# design.net
KiCad netlist of a schematic drawn in Altium Designer
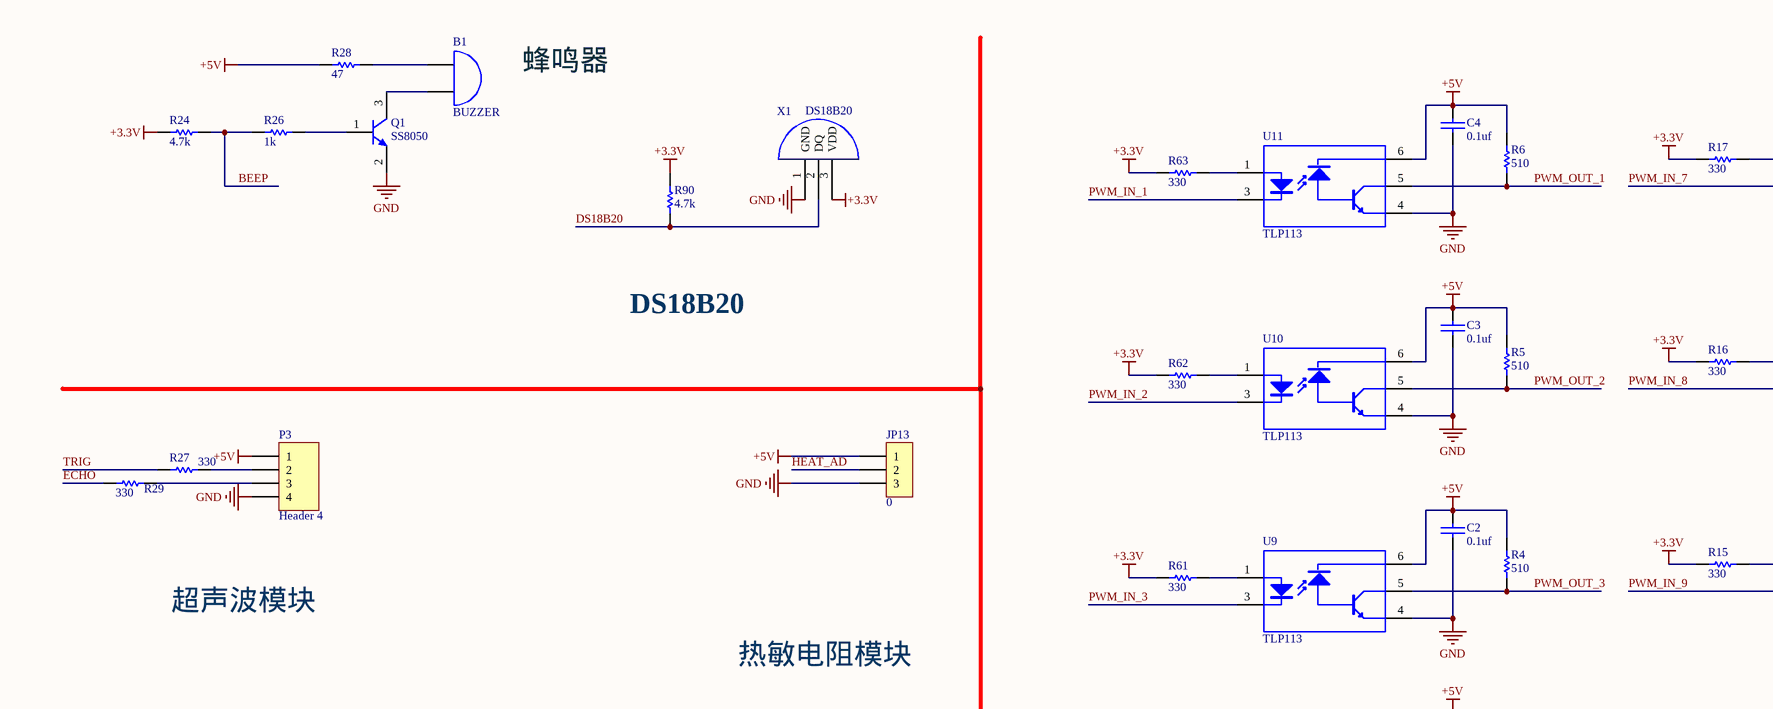
[diagram p0: 原理图.SchDoc, top left]
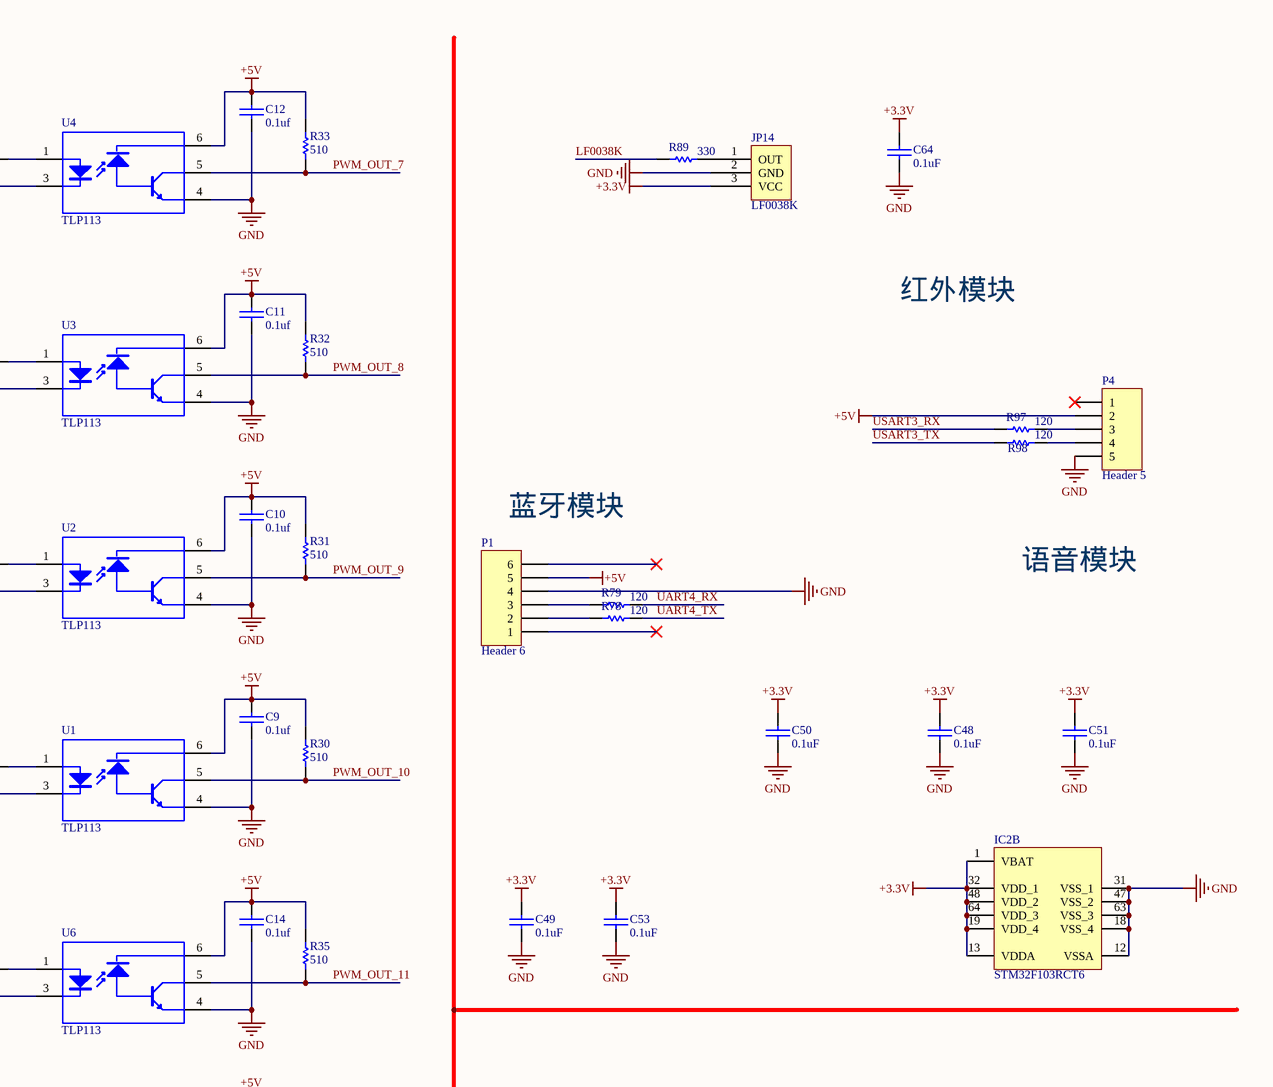
[diagram p1: 原理图.SchDoc, top right]
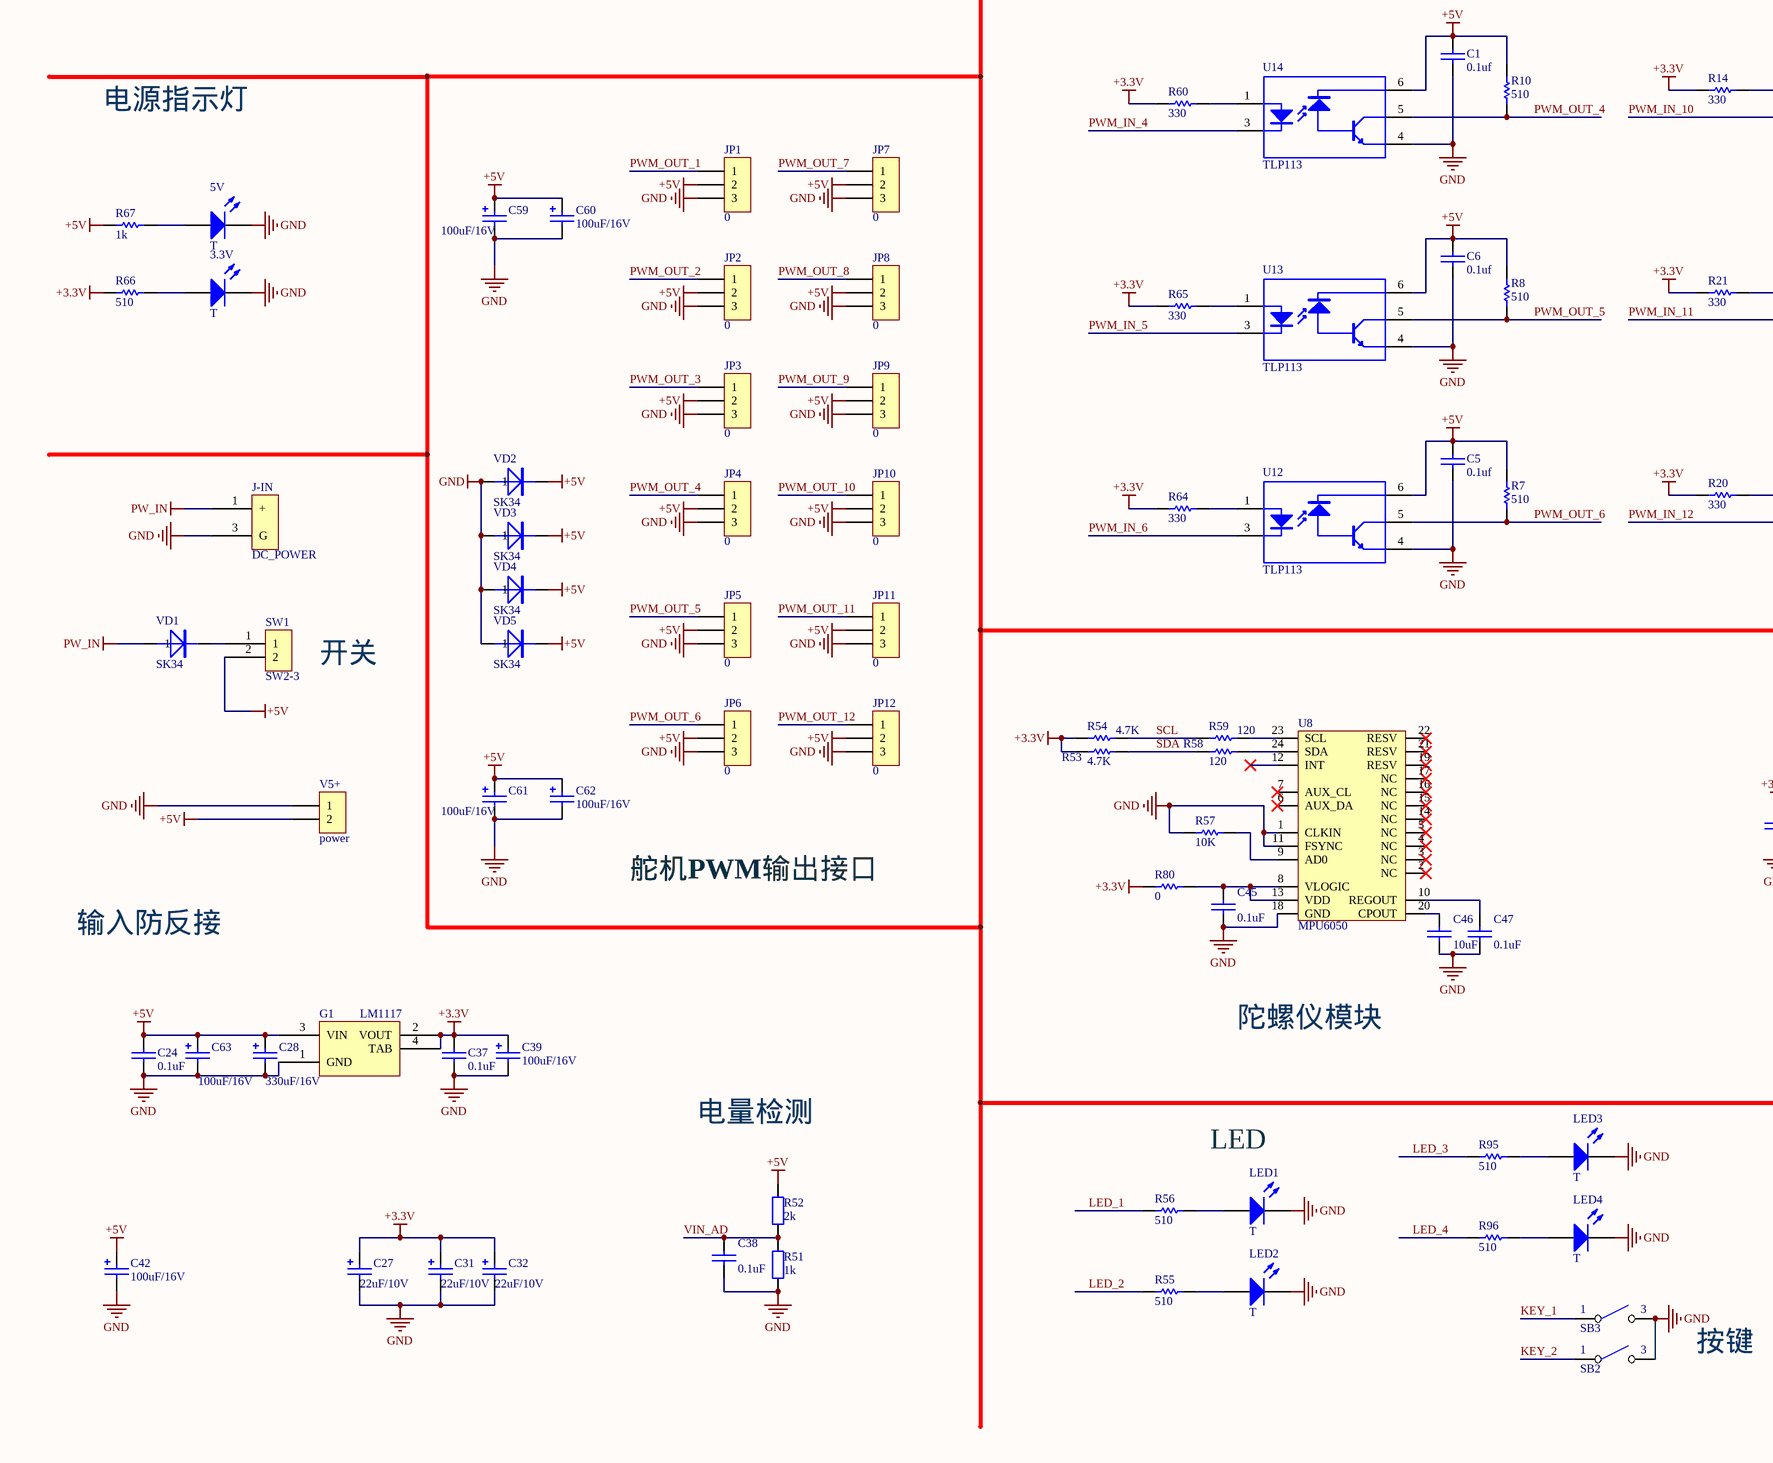
[diagram p2: 原理图.SchDoc, bottom left]
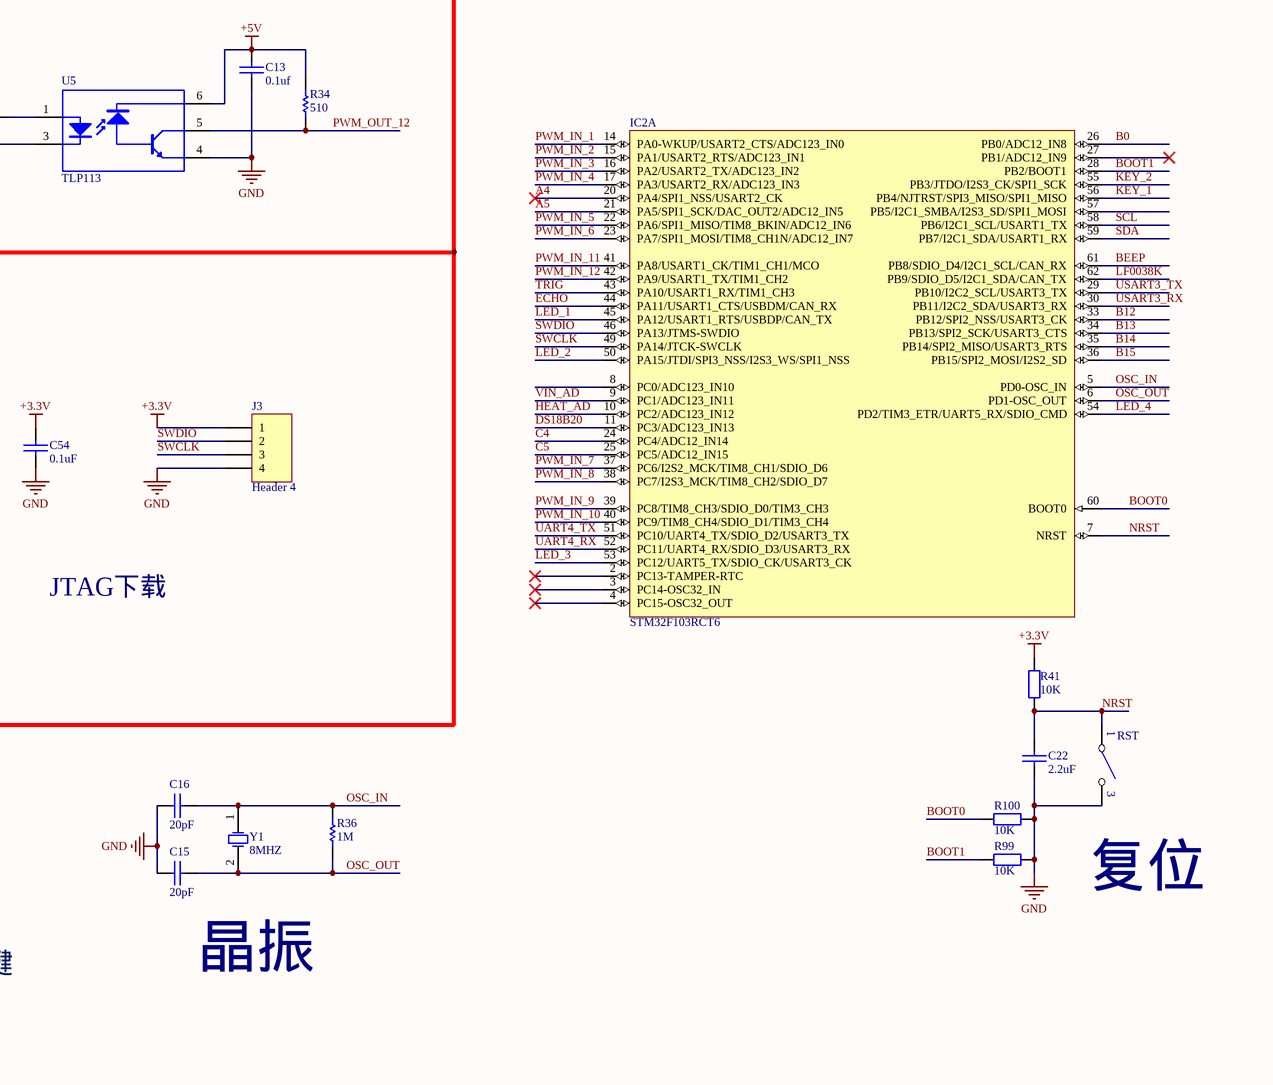
[diagram p3: 原理图.SchDoc, bottom right]

(export (version "E")
  (design (tool "Eeschema 10.0.6"))
  (components
    (comp (ref "3.3V")
      (value "T")
      (footprint "LED-0805")
      (description "Typical INFRARED GaAs LED")
      (fields (field (name "PUBLISHER") "Altium Limited"))
      (libsource (lib "Integrated_Library_1") (part "LED0"))
    )
    (comp (ref "5V")
      (value "T")
      (footprint "LED-0805")
      (description "Typical INFRARED GaAs LED")
      (fields (field (name "PUBLISHER") "Altium Limited"))
      (libsource (lib "Integrated_Library_1") (part "LED0"))
    )
    (comp (ref "B1")
      (value "BUZZER")
      (footprint "BUZZER-5V")
      (description "Bell")
      (libsource (lib "Integrated_Library_1") (part "BELL"))
    )
    (comp (ref "C1")
      (value "0.1uf")
      (footprint "0805")
      (libsource (lib "Integrated_Library_1") (part "CAP_1"))
    )
    (comp (ref "C2")
      (value "0.1uf")
      (footprint "0805")
      (libsource (lib "Integrated_Library_1") (part "CAP_1"))
    )
    (comp (ref "C3")
      (value "0.1uf")
      (footprint "0805")
      (libsource (lib "Integrated_Library_1") (part "CAP_1"))
    )
    (comp (ref "C4")
      (value "0.1uf")
      (footprint "0805")
      (libsource (lib "Integrated_Library_1") (part "CAP_1"))
    )
    (comp (ref "C5")
      (value "0.1uf")
      (footprint "0805")
      (libsource (lib "Integrated_Library_1") (part "CAP_1"))
    )
    (comp (ref "C6")
      (value "0.1uf")
      (footprint "0805")
      (libsource (lib "Integrated_Library_1") (part "CAP_1"))
    )
    (comp (ref "C9")
      (value "0.1uf")
      (footprint "0805")
      (libsource (lib "Integrated_Library_1") (part "CAP_1"))
    )
    (comp (ref "C10")
      (value "0.1uf")
      (footprint "0805")
      (libsource (lib "Integrated_Library_1") (part "CAP_1"))
    )
    (comp (ref "C11")
      (value "0.1uf")
      (footprint "0805")
      (libsource (lib "Integrated_Library_1") (part "CAP_1"))
    )
    (comp (ref "C12")
      (value "0.1uf")
      (footprint "0805")
      (libsource (lib "Integrated_Library_1") (part "CAP_1"))
    )
    (comp (ref "C13")
      (value "0.1uf")
      (footprint "0805")
      (libsource (lib "Integrated_Library_1") (part "CAP_1"))
    )
    (comp (ref "C14")
      (value "0.1uf")
      (footprint "0805")
      (libsource (lib "Integrated_Library_1") (part "CAP_1"))
    )
    (comp (ref "C15")
      (value "20pF")
      (footprint "0805")
      (libsource (lib "Integrated_Library_1") (part "CAP_1"))
    )
    (comp (ref "C16")
      (value "20pF")
      (footprint "0805")
      (libsource (lib "Integrated_Library_1") (part "CAP_1"))
    )
    (comp (ref "C22")
      (value "2.2uF")
      (footprint "0805")
      (libsource (lib "Integrated_Library_1") (part "CAP"))
    )
    (comp (ref "C24")
      (value "0.1uF")
      (footprint "0805")
      (libsource (lib "Integrated_Library_1") (part "CAP_1"))
    )
    (comp (ref "C27")
      (value "22uF/10V")
      (footprint "3528-B")
      (description "Capacitor")
      (libsource (lib "Integrated_Library_1") (part "ELECTRO1"))
    )
    (comp (ref "C28")
      (value "330uF/16V")
      (footprint "CSMD-100U50V")
      (description "Capacitor")
      (libsource (lib "Integrated_Library_1") (part "ELECTRO1"))
    )
    (comp (ref "C31")
      (value "22uF/10V")
      (footprint "3528-B")
      (description "Capacitor")
      (libsource (lib "Integrated_Library_1") (part "ELECTRO1"))
    )
    (comp (ref "C32")
      (value "22uF/10V")
      (footprint "3528-B")
      (description "Capacitor")
      (libsource (lib "Integrated_Library_1") (part "ELECTRO1"))
    )
    (comp (ref "C37")
      (value "0.1uF")
      (footprint "0805")
      (libsource (lib "Integrated_Library_1") (part "CAP_1"))
    )
    (comp (ref "C38")
      (value "0.1uF")
      (footprint "0805")
      (libsource (lib "Integrated_Library_1") (part "CAP_1"))
    )
    (comp (ref "C39")
      (value "100uF/16V")
      (footprint "7243-D")
      (description "Capacitor")
      (libsource (lib "Integrated_Library_1") (part "ELECTRO1"))
    )
    (comp (ref "C42")
      (value "100uF/16V")
      (footprint "7243-D")
      (description "Capacitor")
      (libsource (lib "Integrated_Library_1") (part "ELECTRO1"))
    )
    (comp (ref "C45")
      (value "0.1uF")
      (footprint "0805")
      (libsource (lib "Integrated_Library_1") (part "CAP_1"))
    )
    (comp (ref "C46")
      (value "10uF")
      (footprint "0805")
      (libsource (lib "Integrated_Library_1") (part "CAP_1"))
    )
    (comp (ref "C47")
      (value "0.1uF")
      (footprint "0805")
      (libsource (lib "Integrated_Library_1") (part "CAP_1"))
    )
    (comp (ref "C48")
      (value "0.1uF")
      (footprint "0805")
      (libsource (lib "Integrated_Library_1") (part "CAP"))
    )
    (comp (ref "C49")
      (value "0.1uF")
      (footprint "0805")
      (libsource (lib "Integrated_Library_1") (part "CAP"))
    )
    (comp (ref "C50")
      (value "0.1uF")
      (footprint "0805")
      (libsource (lib "Integrated_Library_1") (part "CAP"))
    )
    (comp (ref "C51")
      (value "0.1uF")
      (footprint "0805")
      (libsource (lib "Integrated_Library_1") (part "CAP"))
    )
    (comp (ref "C53")
      (value "0.1uF")
      (footprint "0805")
      (libsource (lib "Integrated_Library_1") (part "CAP"))
    )
    (comp (ref "C54")
      (value "0.1uF")
      (footprint "0805")
      (libsource (lib "Integrated_Library_1") (part "CAP"))
    )
    (comp (ref "C59")
      (value "100uF/16V")
      (footprint "7243-D")
      (description "Capacitor")
      (libsource (lib "Integrated_Library_1") (part "ELECTRO1"))
    )
    (comp (ref "C60")
      (value "100uF/16V")
      (footprint "7243-D")
      (description "Capacitor")
      (libsource (lib "Integrated_Library_1") (part "ELECTRO1"))
    )
    (comp (ref "C61")
      (value "100uF/16V")
      (footprint "7243-D")
      (description "Capacitor")
      (libsource (lib "Integrated_Library_1") (part "ELECTRO1"))
    )
    (comp (ref "C62")
      (value "100uF/16V")
      (footprint "7243-D")
      (description "Capacitor")
      (libsource (lib "Integrated_Library_1") (part "ELECTRO1"))
    )
    (comp (ref "C63")
      (value "100uF/16V")
      (footprint "7243-D")
      (description "Capacitor")
      (libsource (lib "Integrated_Library_1") (part "ELECTRO1"))
    )
    (comp (ref "C64")
      (value "0.1uF")
      (footprint "0805")
      (libsource (lib "Integrated_Library_1") (part "CAP"))
    )
    (comp (ref "G1") (value "LM1117") (footprint "SOT223-2.3") (libsource (lib "EIC-Sch-N") (part "LM1117")))
    (comp (ref "IC2")
      (value "STM32F103RCT6")
      (footprint "TQFP64-0.5")
      (libsource (lib "altium-import") (part "root_0_STM32F103RCT6_"))
    )
    (comp (ref "J-IN")
      (value "DC_POWER")
      (footprint "DC-005 5.5-2.1")
      (libsource (lib "Integrated_Library_1") (part "DC_POWER"))
    )
    (comp (ref "J3")
      (value "Header 4")
      (footprint "HDR1X4")
      (description "Header, 4-Pin")
      (fields (field (name "PUBLISHER") "Altium Limited"))
      (libsource (lib "Miscellaneous Connectors") (part "Header 4"))
    )
    (comp (ref "JP1")
      (value "0")
      (footprint "SIP3-2.54")
      (description "Connector")
      (libsource (lib "Integrated_Library_1") (part "CON3"))
    )
    (comp (ref "JP2")
      (value "0")
      (footprint "SIP3-2.54")
      (description "Connector")
      (libsource (lib "Integrated_Library_1") (part "CON3"))
    )
    (comp (ref "JP3")
      (value "0")
      (footprint "SIP3-2.54")
      (description "Connector")
      (libsource (lib "Integrated_Library_1") (part "CON3"))
    )
    (comp (ref "JP4")
      (value "0")
      (footprint "SIP3-2.54")
      (description "Connector")
      (libsource (lib "Integrated_Library_1") (part "CON3"))
    )
    (comp (ref "JP5")
      (value "0")
      (footprint "SIP3-2.54")
      (description "Connector")
      (libsource (lib "Integrated_Library_1") (part "CON3"))
    )
    (comp (ref "JP6")
      (value "0")
      (footprint "SIP3-2.54")
      (description "Connector")
      (libsource (lib "Integrated_Library_1") (part "CON3"))
    )
    (comp (ref "JP7")
      (value "0")
      (footprint "SIP3-2.54")
      (description "Connector")
      (libsource (lib "Integrated_Library_1") (part "CON3"))
    )
    (comp (ref "JP8")
      (value "0")
      (footprint "SIP3-2.54")
      (description "Connector")
      (libsource (lib "Integrated_Library_1") (part "CON3"))
    )
    (comp (ref "JP9")
      (value "0")
      (footprint "SIP3-2.54")
      (description "Connector")
      (libsource (lib "Integrated_Library_1") (part "CON3"))
    )
    (comp (ref "JP10")
      (value "0")
      (footprint "SIP3-2.54")
      (description "Connector")
      (libsource (lib "Integrated_Library_1") (part "CON3"))
    )
    (comp (ref "JP11")
      (value "0")
      (footprint "SIP3-2.54")
      (description "Connector")
      (libsource (lib "Integrated_Library_1") (part "CON3"))
    )
    (comp (ref "JP12")
      (value "0")
      (footprint "SIP3-2.54")
      (description "Connector")
      (libsource (lib "Integrated_Library_1") (part "CON3"))
    )
    (comp (ref "JP13")
      (value "0")
      (footprint "SIP3-2.54")
      (description "Connector")
      (libsource (lib "Integrated_Library_1") (part "CON3"))
    )
    (comp (ref "JP14")
      (value "LF0038K")
      (footprint "LF0038K")
      (libsource (lib "Integrated_Library_1") (part "LF0038K"))
    )
    (comp (ref "LED1")
      (value "T")
      (footprint "LED-0805")
      (description "Typical INFRARED GaAs LED")
      (fields (field (name "PUBLISHER") "Altium Limited"))
      (libsource (lib "Integrated_Library_1") (part "LED0"))
    )
    (comp (ref "LED2")
      (value "T")
      (footprint "LED-0805")
      (description "Typical INFRARED GaAs LED")
      (fields (field (name "PUBLISHER") "Altium Limited"))
      (libsource (lib "Integrated_Library_1") (part "LED0"))
    )
    (comp (ref "LED3")
      (value "T")
      (footprint "LED-0805")
      (description "Typical INFRARED GaAs LED")
      (fields (field (name "PUBLISHER") "Altium Limited"))
      (libsource (lib "Integrated_Library_1") (part "LED0"))
    )
    (comp (ref "LED4")
      (value "T")
      (footprint "LED-0805")
      (description "Typical INFRARED GaAs LED")
      (fields (field (name "PUBLISHER") "Altium Limited"))
      (libsource (lib "Integrated_Library_1") (part "LED0"))
    )
    (comp (ref "P1")
      (value "Header 6")
      (footprint "HDR1X6")
      (description "Header, 6-Pin")
      (fields (field (name "PUBLISHER") "Altium Limited"))
      (libsource (lib "Miscellaneous Connectors") (part "Header 6"))
    )
    (comp (ref "P3")
      (value "Header 4")
      (footprint "HDR1X4")
      (description "Header, 4-Pin")
      (fields (field (name "PUBLISHER") "Altium Limited"))
      (libsource (lib "Miscellaneous Connectors") (part "Header 4"))
    )
    (comp (ref "P4")
      (value "Header 5")
      (footprint "HDR1X5")
      (description "Header, 5-Pin")
      (fields (field (name "PUBLISHER") "Altium Limited"))
      (libsource (lib "Miscellaneous Connectors") (part "Header 5"))
    )
    (comp (ref "Q1")
      (value "SS8050")
      (footprint "SOT-23")
      (description "NPN贴片三极管")
      (fields (field (name "PUBLISHER") "Altium Limited"))
      (libsource (lib "Integrated_Library_1") (part "SS8050"))
    )
    (comp (ref "R4")
      (value "510")
      (footprint "0805")
      (description "Resistor")
      (fields (field (name "PUBLISHER") "Altium Limited"))
      (libsource (lib "Integrated_Library_1") (part "Res1"))
    )
    (comp (ref "R5")
      (value "510")
      (footprint "0805")
      (description "Resistor")
      (fields (field (name "PUBLISHER") "Altium Limited"))
      (libsource (lib "Integrated_Library_1") (part "Res1"))
    )
    (comp (ref "R6")
      (value "510")
      (footprint "0805")
      (description "Resistor")
      (fields (field (name "PUBLISHER") "Altium Limited"))
      (libsource (lib "Integrated_Library_1") (part "Res1"))
    )
    (comp (ref "R7")
      (value "510")
      (footprint "0805")
      (description "Resistor")
      (fields (field (name "PUBLISHER") "Altium Limited"))
      (libsource (lib "Integrated_Library_1") (part "Res1"))
    )
    (comp (ref "R8")
      (value "510")
      (footprint "0805")
      (description "Resistor")
      (fields (field (name "PUBLISHER") "Altium Limited"))
      (libsource (lib "Integrated_Library_1") (part "Res1"))
    )
    (comp (ref "R10")
      (value "510")
      (footprint "0805")
      (description "Resistor")
      (fields (field (name "PUBLISHER") "Altium Limited"))
      (libsource (lib "Integrated_Library_1") (part "Res1"))
    )
    (comp (ref "R14")
      (value "330")
      (footprint "0805")
      (description "Resistor")
      (fields (field (name "PUBLISHER") "Altium Limited"))
      (libsource (lib "Integrated_Library_1") (part "Res1"))
    )
    (comp (ref "R15")
      (value "330")
      (footprint "0805")
      (description "Resistor")
      (fields (field (name "PUBLISHER") "Altium Limited"))
      (libsource (lib "Integrated_Library_1") (part "Res1"))
    )
    (comp (ref "R16")
      (value "330")
      (footprint "0805")
      (description "Resistor")
      (fields (field (name "PUBLISHER") "Altium Limited"))
      (libsource (lib "Integrated_Library_1") (part "Res1"))
    )
    (comp (ref "R17")
      (value "330")
      (footprint "0805")
      (description "Resistor")
      (fields (field (name "PUBLISHER") "Altium Limited"))
      (libsource (lib "Integrated_Library_1") (part "Res1"))
    )
    (comp (ref "R20")
      (value "330")
      (footprint "0805")
      (description "Resistor")
      (fields (field (name "PUBLISHER") "Altium Limited"))
      (libsource (lib "Integrated_Library_1") (part "Res1"))
    )
    (comp (ref "R21")
      (value "330")
      (footprint "0805")
      (description "Resistor")
      (fields (field (name "PUBLISHER") "Altium Limited"))
      (libsource (lib "Integrated_Library_1") (part "Res1"))
    )
    (comp (ref "R24")
      (value "4.7k")
      (footprint "0805")
      (description "Resistor")
      (fields (field (name "PUBLISHER") "Altium Limited"))
      (libsource (lib "Integrated_Library_1") (part "Res1"))
    )
    (comp (ref "R26")
      (value "1k")
      (footprint "0805")
      (description "Resistor")
      (fields (field (name "PUBLISHER") "Altium Limited"))
      (libsource (lib "Integrated_Library_1") (part "Res1"))
    )
    (comp (ref "R27")
      (value "330")
      (footprint "0805")
      (description "Resistor")
      (fields (field (name "PUBLISHER") "Altium Limited"))
      (libsource (lib "Integrated_Library_1") (part "Res1"))
    )
    (comp (ref "R28")
      (value "47")
      (footprint "0805")
      (description "Resistor")
      (fields (field (name "PUBLISHER") "Altium Limited"))
      (libsource (lib "Integrated_Library_1") (part "Res1"))
    )
    (comp (ref "R29")
      (value "330")
      (footprint "0805")
      (description "Resistor")
      (fields (field (name "PUBLISHER") "Altium Limited"))
      (libsource (lib "Integrated_Library_1") (part "Res1"))
    )
    (comp (ref "R30")
      (value "510")
      (footprint "0805")
      (description "Resistor")
      (fields (field (name "PUBLISHER") "Altium Limited"))
      (libsource (lib "Integrated_Library_1") (part "Res1"))
    )
    (comp (ref "R31")
      (value "510")
      (footprint "0805")
      (description "Resistor")
      (fields (field (name "PUBLISHER") "Altium Limited"))
      (libsource (lib "Integrated_Library_1") (part "Res1"))
    )
    (comp (ref "R32")
      (value "510")
      (footprint "0805")
      (description "Resistor")
      (fields (field (name "PUBLISHER") "Altium Limited"))
      (libsource (lib "Integrated_Library_1") (part "Res1"))
    )
    (comp (ref "R33")
      (value "510")
      (footprint "0805")
      (description "Resistor")
      (fields (field (name "PUBLISHER") "Altium Limited"))
      (libsource (lib "Integrated_Library_1") (part "Res1"))
    )
    (comp (ref "R34")
      (value "510")
      (footprint "0805")
      (description "Resistor")
      (fields (field (name "PUBLISHER") "Altium Limited"))
      (libsource (lib "Integrated_Library_1") (part "Res1"))
    )
    (comp (ref "R35")
      (value "510")
      (footprint "0805")
      (description "Resistor")
      (fields (field (name "PUBLISHER") "Altium Limited"))
      (libsource (lib "Integrated_Library_1") (part "Res1"))
    )
    (comp (ref "R36")
      (value "1M")
      (footprint "0805")
      (description "Resistor")
      (fields (field (name "PUBLISHER") "Altium Limited"))
      (libsource (lib "Integrated_Library_1") (part "Res1"))
    )
    (comp (ref "R41")
      (value "10K")
      (footprint "0805")
      (description "Resistor")
      (fields (field (name "PUBLISHER") "Altium Limited"))
      (libsource (lib "Miscellaneous Devices") (part "RES1"))
    )
    (comp (ref "R51")
      (value "1k")
      (footprint "0805")
      (description "Resistor")
      (fields (field (name "PUBLISHER") "Altium Limited"))
      (libsource (lib "Miscellaneous Devices") (part "Res2"))
    )
    (comp (ref "R52")
      (value "2k")
      (footprint "0805")
      (description "Resistor")
      (fields (field (name "PUBLISHER") "Altium Limited"))
      (libsource (lib "Miscellaneous Devices") (part "Res2"))
    )
    (comp (ref "R53")
      (value "4.7K")
      (footprint "0805")
      (description "Resistor")
      (fields (field (name "PUBLISHER") "Altium Limited"))
      (libsource (lib "Integrated_Library_1") (part "Res1"))
    )
    (comp (ref "R54")
      (value "4.7K")
      (footprint "0805")
      (description "Resistor")
      (fields (field (name "PUBLISHER") "Altium Limited"))
      (libsource (lib "Integrated_Library_1") (part "Res1"))
    )
    (comp (ref "R55")
      (value "510")
      (footprint "0805")
      (description "Resistor")
      (fields (field (name "PUBLISHER") "Altium Limited"))
      (libsource (lib "Integrated_Library_1") (part "Res1"))
    )
    (comp (ref "R56")
      (value "510")
      (footprint "0805")
      (description "Resistor")
      (fields (field (name "PUBLISHER") "Altium Limited"))
      (libsource (lib "Integrated_Library_1") (part "Res1"))
    )
    (comp (ref "R57")
      (value "10K")
      (footprint "0805")
      (description "Resistor")
      (fields (field (name "PUBLISHER") "Altium Limited"))
      (libsource (lib "Integrated_Library_1") (part "Res1"))
    )
    (comp (ref "R58")
      (value "120")
      (footprint "0805")
      (description "Resistor")
      (fields (field (name "PUBLISHER") "Altium Limited"))
      (libsource (lib "Integrated_Library_1") (part "Res1"))
    )
    (comp (ref "R59")
      (value "120")
      (footprint "0805")
      (description "Resistor")
      (fields (field (name "PUBLISHER") "Altium Limited"))
      (libsource (lib "Integrated_Library_1") (part "Res1"))
    )
    (comp (ref "R60")
      (value "330")
      (footprint "0805")
      (description "Resistor")
      (fields (field (name "PUBLISHER") "Altium Limited"))
      (libsource (lib "Integrated_Library_1") (part "Res1"))
    )
    (comp (ref "R61")
      (value "330")
      (footprint "0805")
      (description "Resistor")
      (fields (field (name "PUBLISHER") "Altium Limited"))
      (libsource (lib "Integrated_Library_1") (part "Res1"))
    )
    (comp (ref "R62")
      (value "330")
      (footprint "0805")
      (description "Resistor")
      (fields (field (name "PUBLISHER") "Altium Limited"))
      (libsource (lib "Integrated_Library_1") (part "Res1"))
    )
    (comp (ref "R63")
      (value "330")
      (footprint "0805")
      (description "Resistor")
      (fields (field (name "PUBLISHER") "Altium Limited"))
      (libsource (lib "Integrated_Library_1") (part "Res1"))
    )
    (comp (ref "R64")
      (value "330")
      (footprint "0805")
      (description "Resistor")
      (fields (field (name "PUBLISHER") "Altium Limited"))
      (libsource (lib "Integrated_Library_1") (part "Res1"))
    )
    (comp (ref "R65")
      (value "330")
      (footprint "0805")
      (description "Resistor")
      (fields (field (name "PUBLISHER") "Altium Limited"))
      (libsource (lib "Integrated_Library_1") (part "Res1"))
    )
    (comp (ref "R66")
      (value "510")
      (footprint "0805")
      (description "Resistor")
      (fields (field (name "PUBLISHER") "Altium Limited"))
      (libsource (lib "Integrated_Library_1") (part "Res1"))
    )
    (comp (ref "R67")
      (value "1k")
      (footprint "0805")
      (description "Resistor")
      (fields (field (name "PUBLISHER") "Altium Limited"))
      (libsource (lib "Integrated_Library_1") (part "Res1"))
    )
    (comp (ref "R78")
      (value "120")
      (footprint "0805")
      (description "Resistor")
      (fields (field (name "PUBLISHER") "Altium Limited"))
      (libsource (lib "Integrated_Library_1") (part "Res1"))
    )
    (comp (ref "R79")
      (value "120")
      (footprint "0805")
      (description "Resistor")
      (fields (field (name "PUBLISHER") "Altium Limited"))
      (libsource (lib "Integrated_Library_1") (part "Res1"))
    )
    (comp (ref "R80")
      (value "0")
      (footprint "0805")
      (description "Resistor")
      (fields (field (name "PUBLISHER") "Altium Limited"))
      (libsource (lib "Integrated_Library_1") (part "Res1"))
    )
    (comp (ref "R89")
      (value "330")
      (footprint "0805")
      (description "Resistor")
      (fields (field (name "PUBLISHER") "Altium Limited"))
      (libsource (lib "Integrated_Library_1") (part "Res1"))
    )
    (comp (ref "R90")
      (value "4.7k")
      (footprint "0805")
      (description "Resistor")
      (fields (field (name "PUBLISHER") "Altium Limited"))
      (libsource (lib "Integrated_Library_1") (part "Res1"))
    )
    (comp (ref "R95")
      (value "510")
      (footprint "0805")
      (description "Resistor")
      (fields (field (name "PUBLISHER") "Altium Limited"))
      (libsource (lib "Integrated_Library_1") (part "Res1"))
    )
    (comp (ref "R96")
      (value "510")
      (footprint "0805")
      (description "Resistor")
      (fields (field (name "PUBLISHER") "Altium Limited"))
      (libsource (lib "Integrated_Library_1") (part "Res1"))
    )
    (comp (ref "R97")
      (value "120")
      (footprint "0805")
      (description "Resistor")
      (fields (field (name "PUBLISHER") "Altium Limited"))
      (libsource (lib "Integrated_Library_1") (part "Res1"))
    )
    (comp (ref "R98")
      (value "120")
      (footprint "0805")
      (description "Resistor")
      (fields (field (name "PUBLISHER") "Altium Limited"))
      (libsource (lib "Integrated_Library_1") (part "Res1"))
    )
    (comp (ref "R99")
      (value "10K")
      (footprint "0805")
      (description "Resistor")
      (fields (field (name "PUBLISHER") "Altium Limited"))
      (libsource (lib "") (part "RES1_1"))
    )
    (comp (ref "R100")
      (value "10K")
      (footprint "0805")
      (description "Resistor")
      (fields (field (name "PUBLISHER") "Altium Limited"))
      (libsource (lib "") (part "RES1_1"))
    )
    (comp (ref "RST")
      (value "Config")
      (footprint "KEY-SMD")
      (libsource (lib "Integrated_Library_1") (part "KEY1"))
    )
    (comp (ref "SB2")
      (value "Config")
      (footprint "KEY-SMD")
      (libsource (lib "Integrated_Library_1") (part "KEY1"))
    )
    (comp (ref "SB3")
      (value "Config")
      (footprint "KEY-SMD")
      (libsource (lib "Integrated_Library_1") (part "KEY1"))
    )
    (comp (ref "SW1")
      (value "SW2-3")
      (footprint "SS-12F44(1P2T)")
      (libsource (lib "Integrated_Library_1") (part "SW2-3"))
    )
    (comp (ref "U1")
      (value "TLP113")
      (footprint "MFSOP6-5")
      (description "Optoisolator")
      (libsource (lib "Integrated_Library_1") (part "TLP113"))
    )
    (comp (ref "U2")
      (value "TLP113")
      (footprint "MFSOP6-5")
      (description "Optoisolator")
      (libsource (lib "Integrated_Library_1") (part "TLP113"))
    )
    (comp (ref "U3")
      (value "TLP113")
      (footprint "MFSOP6-5")
      (description "Optoisolator")
      (libsource (lib "Integrated_Library_1") (part "TLP113"))
    )
    (comp (ref "U4")
      (value "TLP113")
      (footprint "MFSOP6-5")
      (description "Optoisolator")
      (libsource (lib "Integrated_Library_1") (part "TLP113"))
    )
    (comp (ref "U5")
      (value "TLP113")
      (footprint "MFSOP6-5")
      (description "Optoisolator")
      (libsource (lib "Integrated_Library_1") (part "TLP113"))
    )
    (comp (ref "U6")
      (value "TLP113")
      (footprint "MFSOP6-5")
      (description "Optoisolator")
      (libsource (lib "Integrated_Library_1") (part "TLP113"))
    )
    (comp (ref "U8")
      (value "MPU6050")
      (footprint "QFN24")
      (description "9轴运动处理传感器")
      (libsource (lib "ATK-MPU6050六轴传感器模块") (part "MPU6050"))
    )
    (comp (ref "U9")
      (value "TLP113")
      (footprint "MFSOP6-5")
      (description "Optoisolator")
      (libsource (lib "Integrated_Library_1") (part "TLP113"))
    )
    (comp (ref "U10")
      (value "TLP113")
      (footprint "MFSOP6-5")
      (description "Optoisolator")
      (libsource (lib "Integrated_Library_1") (part "TLP113"))
    )
    (comp (ref "U11")
      (value "TLP113")
      (footprint "MFSOP6-5")
      (description "Optoisolator")
      (libsource (lib "Integrated_Library_1") (part "TLP113"))
    )
    (comp (ref "U12")
      (value "TLP113")
      (footprint "MFSOP6-5")
      (description "Optoisolator")
      (libsource (lib "Integrated_Library_1") (part "TLP113"))
    )
    (comp (ref "U13")
      (value "TLP113")
      (footprint "MFSOP6-5")
      (description "Optoisolator")
      (libsource (lib "Integrated_Library_1") (part "TLP113"))
    )
    (comp (ref "U14")
      (value "TLP113")
      (footprint "MFSOP6-5")
      (description "Optoisolator")
      (libsource (lib "Integrated_Library_1") (part "TLP113"))
    )
    (comp (ref "V5+")
      (value "power")
      (footprint "MKDS2-5.08")
      (description "Connector")
      (libsource (lib "Integrated_Library_1") (part "CON2"))
    )
    (comp (ref "VD1")
      (value "SK34")
      (footprint "SK34-DIODE")
      (libsource (lib "Integrated_Library_1") (part "SK34-DIODE"))
    )
    (comp (ref "VD2")
      (value "SK34")
      (footprint "SK34-DIODE")
      (libsource (lib "Integrated_Library_1") (part "SK34-DIODE"))
    )
    (comp (ref "VD3")
      (value "SK34")
      (footprint "SK34-DIODE")
      (libsource (lib "Integrated_Library_1") (part "SK34-DIODE"))
    )
    (comp (ref "VD4")
      (value "SK34")
      (footprint "SK34-DIODE")
      (libsource (lib "Integrated_Library_1") (part "SK34-DIODE"))
    )
    (comp (ref "VD5")
      (value "SK34")
      (footprint "SK34-DIODE")
      (libsource (lib "Integrated_Library_1") (part "SK34-DIODE"))
    )
    (comp (ref "X1")
      (value "DS18B20")
      (footprint "DS18B20TR")
      (libsource (lib "Integrated_Library_1") (part "DS18B20"))
    )
    (comp (ref "Y1")
      (value "8MHZ")
      (footprint "CRYSTAL-2PIN")
      (description "Crystal Oscillator")
      (fields (field (name "PUBLISHER") "Altium Limited"))
      (libsource (lib "Integrated_Library_1") (part "XTAL_1"))
    )
  )
  (nets
    (net (code "1") (name "+3.3V") (class "Default")
      (node (ref "C27") (pin "1") (pinfunction "1_1") (pintype "passive"))
      (node (ref "C31") (pin "1") (pinfunction "1_1") (pintype "passive"))
      (node (ref "C32") (pin "1") (pinfunction "1_1") (pintype "passive"))
      (node (ref "C37") (pin "1") (pintype "passive"))
      (node (ref "C39") (pin "1") (pinfunction "1_1") (pintype "passive"))
      (node (ref "C48") (pin "1") (pintype "passive"))
      (node (ref "C49") (pin "1") (pintype "passive"))
      (node (ref "C50") (pin "1") (pintype "passive"))
      (node (ref "C51") (pin "1") (pintype "passive"))
      (node (ref "C53") (pin "1") (pintype "passive"))
      (node (ref "C54") (pin "1") (pintype "passive"))
      (node (ref "C64") (pin "1") (pintype "passive"))
      (node (ref "G1") (pin "2") (pinfunction "VOUT_2") (pintype "passive"))
      (node (ref "G1") (pin "4") (pinfunction "TAB_4") (pintype "passive"))
      (node (ref "IC2") (pin "1") (pinfunction "VBAT_1") (pintype "power_in"))
      (node (ref "IC2") (pin "13") (pinfunction "VDDA_13") (pintype "power_in"))
      (node (ref "IC2") (pin "19") (pinfunction "VDD_4_19") (pintype "power_in"))
      (node (ref "IC2") (pin "32") (pinfunction "VDD_1_32") (pintype "power_in"))
      (node (ref "IC2") (pin "48") (pinfunction "VDD_2_48") (pintype "power_in"))
      (node (ref "IC2") (pin "64") (pinfunction "VDD_3_64") (pintype "power_in"))
      (node (ref "J3") (pin "1") (pinfunction "1_1") (pintype "passive"))
      (node (ref "JP14") (pin "3") (pinfunction "VCC_3") (pintype "passive"))
      (node (ref "R14") (pin "1") (pinfunction "1_1") (pintype "passive"))
      (node (ref "R15") (pin "1") (pinfunction "1_1") (pintype "passive"))
      (node (ref "R16") (pin "1") (pinfunction "1_1") (pintype "passive"))
      (node (ref "R17") (pin "1") (pinfunction "1_1") (pintype "passive"))
      (node (ref "R20") (pin "1") (pinfunction "1_1") (pintype "passive"))
      (node (ref "R21") (pin "1") (pinfunction "1_1") (pintype "passive"))
      (node (ref "R24") (pin "1") (pinfunction "1_1") (pintype "passive"))
      (node (ref "R41") (pin "2") (pinfunction "2_2") (pintype "passive"))
      (node (ref "R53") (pin "1") (pinfunction "1_1") (pintype "passive"))
      (node (ref "R54") (pin "1") (pinfunction "1_1") (pintype "passive"))
      (node (ref "R60") (pin "1") (pinfunction "1_1") (pintype "passive"))
      (node (ref "R61") (pin "1") (pinfunction "1_1") (pintype "passive"))
      (node (ref "R62") (pin "1") (pinfunction "1_1") (pintype "passive"))
      (node (ref "R63") (pin "1") (pinfunction "1_1") (pintype "passive"))
      (node (ref "R64") (pin "1") (pinfunction "1_1") (pintype "passive"))
      (node (ref "R65") (pin "1") (pinfunction "1_1") (pintype "passive"))
      (node (ref "R66") (pin "1") (pinfunction "1_1") (pintype "passive"))
      (node (ref "R80") (pin "1") (pinfunction "1_1") (pintype "passive"))
      (node (ref "R90") (pin "2") (pinfunction "2_2") (pintype "passive"))
      (node (ref "X1") (pin "3") (pinfunction "VDD_3") (pintype "passive"))
    )
    (net (code "2") (name "+5V") (class "Default")
      (node (ref "C1") (pin "1") (pintype "passive"))
      (node (ref "C10") (pin "1") (pintype "passive"))
      (node (ref "C11") (pin "1") (pintype "passive"))
      (node (ref "C12") (pin "1") (pintype "passive"))
      (node (ref "C13") (pin "1") (pintype "passive"))
      (node (ref "C14") (pin "1") (pintype "passive"))
      (node (ref "C2") (pin "1") (pintype "passive"))
      (node (ref "C24") (pin "1") (pintype "passive"))
      (node (ref "C28") (pin "1") (pinfunction "1_1") (pintype "passive"))
      (node (ref "C3") (pin "1") (pintype "passive"))
      (node (ref "C4") (pin "1") (pintype "passive"))
      (node (ref "C42") (pin "1") (pinfunction "1_1") (pintype "passive"))
      (node (ref "C5") (pin "1") (pintype "passive"))
      (node (ref "C59") (pin "1") (pinfunction "1_1") (pintype "passive"))
      (node (ref "C6") (pin "1") (pintype "passive"))
      (node (ref "C60") (pin "1") (pinfunction "1_1") (pintype "passive"))
      (node (ref "C61") (pin "1") (pinfunction "1_1") (pintype "passive"))
      (node (ref "C62") (pin "1") (pinfunction "1_1") (pintype "passive"))
      (node (ref "C63") (pin "1") (pinfunction "1_1") (pintype "passive"))
      (node (ref "C9") (pin "1") (pintype "passive"))
      (node (ref "G1") (pin "3") (pinfunction "VIN_3") (pintype "passive"))
      (node (ref "JP1") (pin "2") (pinfunction "2_2") (pintype "passive"))
      (node (ref "JP10") (pin "2") (pinfunction "2_2") (pintype "passive"))
      (node (ref "JP11") (pin "2") (pinfunction "2_2") (pintype "passive"))
      (node (ref "JP12") (pin "2") (pinfunction "2_2") (pintype "passive"))
      (node (ref "JP13") (pin "1") (pinfunction "1_1") (pintype "passive"))
      (node (ref "JP2") (pin "2") (pinfunction "2_2") (pintype "passive"))
      (node (ref "JP3") (pin "2") (pinfunction "2_2") (pintype "passive"))
      (node (ref "JP4") (pin "2") (pinfunction "2_2") (pintype "passive"))
      (node (ref "JP5") (pin "2") (pinfunction "2_2") (pintype "passive"))
      (node (ref "JP6") (pin "2") (pinfunction "2_2") (pintype "passive"))
      (node (ref "JP7") (pin "2") (pinfunction "2_2") (pintype "passive"))
      (node (ref "JP8") (pin "2") (pinfunction "2_2") (pintype "passive"))
      (node (ref "JP9") (pin "2") (pinfunction "2_2") (pintype "passive"))
      (node (ref "P1") (pin "5") (pinfunction "5_5") (pintype "passive"))
      (node (ref "P3") (pin "1") (pinfunction "1_1") (pintype "passive"))
      (node (ref "P4") (pin "2") (pinfunction "2_2") (pintype "passive"))
      (node (ref "R10") (pin "2") (pinfunction "2_2") (pintype "passive"))
      (node (ref "R28") (pin "1") (pinfunction "1_1") (pintype "passive"))
      (node (ref "R30") (pin "2") (pinfunction "2_2") (pintype "passive"))
      (node (ref "R31") (pin "2") (pinfunction "2_2") (pintype "passive"))
      (node (ref "R32") (pin "2") (pinfunction "2_2") (pintype "passive"))
      (node (ref "R33") (pin "2") (pinfunction "2_2") (pintype "passive"))
      (node (ref "R34") (pin "2") (pinfunction "2_2") (pintype "passive"))
      (node (ref "R35") (pin "2") (pinfunction "2_2") (pintype "passive"))
      (node (ref "R4") (pin "2") (pinfunction "2_2") (pintype "passive"))
      (node (ref "R5") (pin "2") (pinfunction "2_2") (pintype "passive"))
      (node (ref "R52") (pin "1") (pinfunction "1_1") (pintype "passive"))
      (node (ref "R6") (pin "2") (pinfunction "2_2") (pintype "passive"))
      (node (ref "R67") (pin "1") (pinfunction "1_1") (pintype "passive"))
      (node (ref "R7") (pin "2") (pinfunction "2_2") (pintype "passive"))
      (node (ref "R8") (pin "2") (pinfunction "2_2") (pintype "passive"))
      (node (ref "SW1") (pin "2") (pinfunction "2_2") (pintype "passive"))
      (node (ref "U1") (pin "6") (pinfunction "VCC_6") (pintype "passive"))
      (node (ref "U10") (pin "6") (pinfunction "VCC_6") (pintype "passive"))
      (node (ref "U11") (pin "6") (pinfunction "VCC_6") (pintype "passive"))
      (node (ref "U12") (pin "6") (pinfunction "VCC_6") (pintype "passive"))
      (node (ref "U13") (pin "6") (pinfunction "VCC_6") (pintype "passive"))
      (node (ref "U14") (pin "6") (pinfunction "VCC_6") (pintype "passive"))
      (node (ref "U2") (pin "6") (pinfunction "VCC_6") (pintype "passive"))
      (node (ref "U3") (pin "6") (pinfunction "VCC_6") (pintype "passive"))
      (node (ref "U4") (pin "6") (pinfunction "VCC_6") (pintype "passive"))
      (node (ref "U5") (pin "6") (pinfunction "VCC_6") (pintype "passive"))
      (node (ref "U6") (pin "6") (pinfunction "VCC_6") (pintype "passive"))
      (node (ref "U9") (pin "6") (pinfunction "VCC_6") (pintype "passive"))
      (node (ref "V5+") (pin "2") (pinfunction "2_2") (pintype "passive"))
      (node (ref "VD2") (pin "2") (pinfunction "2_2") (pintype "passive"))
      (node (ref "VD3") (pin "2") (pinfunction "2_2") (pintype "passive"))
      (node (ref "VD4") (pin "2") (pinfunction "2_2") (pintype "passive"))
      (node (ref "VD5") (pin "2") (pinfunction "2_2") (pintype "passive"))
    )
    (net (code "3") (name "/A4") (class "Default")
      (node (ref "IC2") (pin "20") (pinfunction "PA4/SPI1_NSS/USART2_CK_20") (pintype "bidirectional+no_connect"))
    )
    (net (code "4") (name "/A5") (class "Default")
      (node (ref "IC2") (pin "21") (pinfunction "PA5/SPI1_SCK/DAC_OUT2/ADC12_IN5_21") (pintype "bidirectional"))
    )
    (net (code "5") (name "/B0") (class "Default")
      (node (ref "IC2") (pin "26") (pinfunction "PB0/ADC12_IN8_26") (pintype "bidirectional"))
    )
    (net (code "6") (name "/B12") (class "Default")
      (node (ref "IC2") (pin "33") (pinfunction "PB12/SPI2_NSS/USART3_CK_33") (pintype "bidirectional"))
    )
    (net (code "7") (name "/B13") (class "Default")
      (node (ref "IC2") (pin "34") (pinfunction "PB13/SPI2_SCK/USART3_CTS_34") (pintype "bidirectional"))
    )
    (net (code "8") (name "/B14") (class "Default")
      (node (ref "IC2") (pin "35") (pinfunction "PB14/SPI2_MISO/USART3_RTS_35") (pintype "bidirectional"))
    )
    (net (code "9") (name "/B15") (class "Default")
      (node (ref "IC2") (pin "36") (pinfunction "PB15/SPI2_MOSI/I2S2_SD_36") (pintype "bidirectional"))
    )
    (net (code "10") (name "/BEEP") (class "Default")
      (node (ref "IC2") (pin "61") (pinfunction "PB8/SDIO_D4/I2C1_SCL/CAN_RX_61") (pintype "bidirectional"))
      (node (ref "R24") (pin "2") (pinfunction "2_2") (pintype "passive"))
      (node (ref "R26") (pin "1") (pinfunction "1_1") (pintype "passive"))
    )
    (net (code "11") (name "/BOOT0") (class "Default")
      (node (ref "IC2") (pin "60") (pinfunction "BOOT0_60") (pintype "input"))
      (node (ref "R100") (pin "2") (pinfunction "2_2") (pintype "passive"))
    )
    (net (code "12") (name "/BOOT1") (class "Default")
      (node (ref "IC2") (pin "28") (pinfunction "PB2/BOOT1_28") (pintype "bidirectional"))
      (node (ref "R99") (pin "2") (pinfunction "2_2") (pintype "passive"))
    )
    (net (code "13") (name "/C4") (class "Default")
      (node (ref "IC2") (pin "24") (pinfunction "PC4/ADC12_IN14_24") (pintype "bidirectional"))
    )
    (net (code "14") (name "/C5") (class "Default")
      (node (ref "IC2") (pin "25") (pinfunction "PC5/ADC12_IN15_25") (pintype "bidirectional"))
    )
    (net (code "15") (name "/DS18B20") (class "Default")
      (node (ref "IC2") (pin "11") (pinfunction "PC3/ADC123_IN13_11") (pintype "bidirectional"))
      (node (ref "R90") (pin "1") (pinfunction "1_1") (pintype "passive"))
      (node (ref "X1") (pin "2") (pinfunction "DQ_2") (pintype "passive"))
    )
    (net (code "16") (name "/ECHO") (class "Default")
      (node (ref "IC2") (pin "44") (pinfunction "PA11/USART1_CTS/USBDM/CAN_RX_44") (pintype "bidirectional"))
      (node (ref "R29") (pin "1") (pinfunction "1_1") (pintype "passive"))
    )
    (net (code "17") (name "/HEAT_AD") (class "Default")
      (node (ref "IC2") (pin "10") (pinfunction "PC2/ADC123_IN12_10") (pintype "bidirectional"))
      (node (ref "JP13") (pin "2") (pinfunction "2_2") (pintype "passive"))
    )
    (net (code "18") (name "/KEY_1") (class "Default")
      (node (ref "IC2") (pin "56") (pinfunction "PB4/NJTRST/SPI3_MISO/SPI1_MISO_56") (pintype "bidirectional"))
      (node (ref "SB3") (pin "1") (pinfunction "COMMON_1") (pintype "passive"))
    )
    (net (code "19") (name "/KEY_2") (class "Default")
      (node (ref "IC2") (pin "55") (pinfunction "PB3/JTDO/I2S3_CK/SPI1_SCK_55") (pintype "bidirectional"))
      (node (ref "SB2") (pin "1") (pinfunction "COMMON_1") (pintype "passive"))
    )
    (net (code "20") (name "/LED_1") (class "Default")
      (node (ref "IC2") (pin "45") (pinfunction "PA12/USART1_RTS/USBDP/CAN_TX_45") (pintype "bidirectional"))
      (node (ref "R56") (pin "1") (pinfunction "1_1") (pintype "passive"))
    )
    (net (code "21") (name "/LED_2") (class "Default")
      (node (ref "IC2") (pin "50") (pinfunction "PA15/JTDI/SPI3_NSS/I2S3_WS/SPI1_NSS_50") (pintype "bidirectional"))
      (node (ref "R55") (pin "1") (pinfunction "1_1") (pintype "passive"))
    )
    (net (code "22") (name "/LED_3") (class "Default")
      (node (ref "IC2") (pin "53") (pinfunction "PC12/UART5_TX/SDIO_CK/USART3_CK_53") (pintype "bidirectional"))
      (node (ref "R95") (pin "1") (pinfunction "1_1") (pintype "passive"))
    )
    (net (code "23") (name "/LED_4") (class "Default")
      (node (ref "IC2") (pin "54") (pinfunction "PD2/TIM3_ETR/UART5_RX/SDIO_CMD_54") (pintype "bidirectional"))
      (node (ref "R96") (pin "1") (pinfunction "1_1") (pintype "passive"))
    )
    (net (code "24") (name "/LF0038K") (class "Default")
      (node (ref "IC2") (pin "62") (pinfunction "PB9/SDIO_D5/I2C1_SDA/CAN_TX_62") (pintype "bidirectional"))
      (node (ref "R89") (pin "1") (pinfunction "1_1") (pintype "passive"))
    )
    (net (code "25") (name "/NRST") (class "Default")
      (node (ref "C22") (pin "1") (pintype "passive"))
      (node (ref "IC2") (pin "7") (pinfunction "NRST_7") (pintype "bidirectional"))
      (node (ref "R41") (pin "1") (pinfunction "1_1") (pintype "passive"))
      (node (ref "RST") (pin "1") (pinfunction "COMMON_1") (pintype "passive"))
    )
    (net (code "26") (name "/OSC_IN") (class "Default")
      (node (ref "C16") (pin "2") (pintype "passive"))
      (node (ref "IC2") (pin "5") (pinfunction "PD0-OSC_IN_5") (pintype "bidirectional"))
      (node (ref "R36") (pin "2") (pinfunction "2_2") (pintype "passive"))
      (node (ref "Y1") (pin "1") (pinfunction "OSC1_1") (pintype "passive"))
    )
    (net (code "27") (name "/OSC_OUT") (class "Default")
      (node (ref "C15") (pin "2") (pintype "passive"))
      (node (ref "IC2") (pin "6") (pinfunction "PD1-OSC_OUT_6") (pintype "bidirectional"))
      (node (ref "R36") (pin "1") (pinfunction "1_1") (pintype "passive"))
      (node (ref "Y1") (pin "2") (pinfunction "OSC2_2") (pintype "passive"))
    )
    (net (code "28") (name "/PWM_IN_1") (class "Default")
      (node (ref "IC2") (pin "14") (pinfunction "PA0-WKUP/USART2_CTS/ADC123_IN0_14") (pintype "bidirectional"))
      (node (ref "U11") (pin "3") (pinfunction "K_3") (pintype "passive"))
    )
    (net (code "29") (name "/PWM_IN_2") (class "Default")
      (node (ref "IC2") (pin "15") (pinfunction "PA1/USART2_RTS/ADC123_IN1_15") (pintype "bidirectional"))
      (node (ref "U10") (pin "3") (pinfunction "K_3") (pintype "passive"))
    )
    (net (code "30") (name "/PWM_IN_3") (class "Default")
      (node (ref "IC2") (pin "16") (pinfunction "PA2/USART2_TX/ADC123_IN2_16") (pintype "bidirectional"))
      (node (ref "U9") (pin "3") (pinfunction "K_3") (pintype "passive"))
    )
    (net (code "31") (name "/PWM_IN_4") (class "Default")
      (node (ref "IC2") (pin "17") (pinfunction "PA3/USART2_RX/ADC123_IN3_17") (pintype "bidirectional"))
      (node (ref "U14") (pin "3") (pinfunction "K_3") (pintype "passive"))
    )
    (net (code "32") (name "/PWM_IN_5") (class "Default")
      (node (ref "IC2") (pin "22") (pinfunction "PA6/SPI1_MISO/TIM8_BKIN/ADC12_IN6_22") (pintype "bidirectional"))
      (node (ref "U13") (pin "3") (pinfunction "K_3") (pintype "passive"))
    )
    (net (code "33") (name "/PWM_IN_6") (class "Default")
      (node (ref "IC2") (pin "23") (pinfunction "PA7/SPI1_MOSI/TIM8_CH1N/ADC12_IN7_23") (pintype "bidirectional"))
      (node (ref "U12") (pin "3") (pinfunction "K_3") (pintype "passive"))
    )
    (net (code "34") (name "/PWM_IN_7") (class "Default")
      (node (ref "IC2") (pin "37") (pinfunction "PC6/I2S2_MCK/TIM8_CH1/SDIO_D6_37") (pintype "bidirectional"))
      (node (ref "U4") (pin "3") (pinfunction "K_3") (pintype "passive"))
    )
    (net (code "35") (name "/PWM_IN_8") (class "Default")
      (node (ref "IC2") (pin "38") (pinfunction "PC7/I2S3_MCK/TIM8_CH2/SDIO_D7_38") (pintype "bidirectional"))
      (node (ref "U3") (pin "3") (pinfunction "K_3") (pintype "passive"))
    )
    (net (code "36") (name "/PWM_IN_9") (class "Default")
      (node (ref "IC2") (pin "39") (pinfunction "PC8/TIM8_CH3/SDIO_D0/TIM3_CH3_39") (pintype "bidirectional"))
      (node (ref "U2") (pin "3") (pinfunction "K_3") (pintype "passive"))
    )
    (net (code "37") (name "/PWM_IN_10") (class "Default")
      (node (ref "IC2") (pin "40") (pinfunction "PC9/TIM8_CH4/SDIO_D1/TIM3_CH4_40") (pintype "bidirectional"))
      (node (ref "U1") (pin "3") (pinfunction "K_3") (pintype "passive"))
    )
    (net (code "38") (name "/PWM_IN_11") (class "Default")
      (node (ref "IC2") (pin "41") (pinfunction "PA8/USART1_CK/TIM1_CH1/MCO_41") (pintype "bidirectional"))
      (node (ref "U6") (pin "3") (pinfunction "K_3") (pintype "passive"))
    )
    (net (code "39") (name "/PWM_IN_12") (class "Default")
      (node (ref "IC2") (pin "42") (pinfunction "PA9/USART1_TX/TIM1_CH2_42") (pintype "bidirectional"))
      (node (ref "U5") (pin "3") (pinfunction "K_3") (pintype "passive"))
    )
    (net (code "40") (name "/PWM_OUT_1") (class "Default")
      (node (ref "JP1") (pin "1") (pinfunction "1_1") (pintype "passive"))
      (node (ref "R6") (pin "1") (pinfunction "1_1") (pintype "passive"))
      (node (ref "U11") (pin "5") (pinfunction "C_5") (pintype "passive"))
    )
    (net (code "41") (name "/PWM_OUT_2") (class "Default")
      (node (ref "JP2") (pin "1") (pinfunction "1_1") (pintype "passive"))
      (node (ref "R5") (pin "1") (pinfunction "1_1") (pintype "passive"))
      (node (ref "U10") (pin "5") (pinfunction "C_5") (pintype "passive"))
    )
    (net (code "42") (name "/PWM_OUT_3") (class "Default")
      (node (ref "JP3") (pin "1") (pinfunction "1_1") (pintype "passive"))
      (node (ref "R4") (pin "1") (pinfunction "1_1") (pintype "passive"))
      (node (ref "U9") (pin "5") (pinfunction "C_5") (pintype "passive"))
    )
    (net (code "43") (name "/PWM_OUT_4") (class "Default")
      (node (ref "JP4") (pin "1") (pinfunction "1_1") (pintype "passive"))
      (node (ref "R10") (pin "1") (pinfunction "1_1") (pintype "passive"))
      (node (ref "U14") (pin "5") (pinfunction "C_5") (pintype "passive"))
    )
    (net (code "44") (name "/PWM_OUT_5") (class "Default")
      (node (ref "JP5") (pin "1") (pinfunction "1_1") (pintype "passive"))
      (node (ref "R8") (pin "1") (pinfunction "1_1") (pintype "passive"))
      (node (ref "U13") (pin "5") (pinfunction "C_5") (pintype "passive"))
    )
    (net (code "45") (name "/PWM_OUT_6") (class "Default")
      (node (ref "JP6") (pin "1") (pinfunction "1_1") (pintype "passive"))
      (node (ref "R7") (pin "1") (pinfunction "1_1") (pintype "passive"))
      (node (ref "U12") (pin "5") (pinfunction "C_5") (pintype "passive"))
    )
    (net (code "46") (name "/PWM_OUT_7") (class "Default")
      (node (ref "JP7") (pin "1") (pinfunction "1_1") (pintype "passive"))
      (node (ref "R33") (pin "1") (pinfunction "1_1") (pintype "passive"))
      (node (ref "U4") (pin "5") (pinfunction "C_5") (pintype "passive"))
    )
    (net (code "47") (name "/PWM_OUT_8") (class "Default")
      (node (ref "JP8") (pin "1") (pinfunction "1_1") (pintype "passive"))
      (node (ref "R32") (pin "1") (pinfunction "1_1") (pintype "passive"))
      (node (ref "U3") (pin "5") (pinfunction "C_5") (pintype "passive"))
    )
    (net (code "48") (name "/PWM_OUT_9") (class "Default")
      (node (ref "JP9") (pin "1") (pinfunction "1_1") (pintype "passive"))
      (node (ref "R31") (pin "1") (pinfunction "1_1") (pintype "passive"))
      (node (ref "U2") (pin "5") (pinfunction "C_5") (pintype "passive"))
    )
    (net (code "49") (name "/PWM_OUT_10") (class "Default")
      (node (ref "JP10") (pin "1") (pinfunction "1_1") (pintype "passive"))
      (node (ref "R30") (pin "1") (pinfunction "1_1") (pintype "passive"))
      (node (ref "U1") (pin "5") (pinfunction "C_5") (pintype "passive"))
    )
    (net (code "50") (name "/PWM_OUT_11") (class "Default")
      (node (ref "JP11") (pin "1") (pinfunction "1_1") (pintype "passive"))
      (node (ref "R35") (pin "1") (pinfunction "1_1") (pintype "passive"))
      (node (ref "U6") (pin "5") (pinfunction "C_5") (pintype "passive"))
    )
    (net (code "51") (name "/PWM_OUT_12") (class "Default")
      (node (ref "JP12") (pin "1") (pinfunction "1_1") (pintype "passive"))
      (node (ref "R34") (pin "1") (pinfunction "1_1") (pintype "passive"))
      (node (ref "U5") (pin "5") (pinfunction "C_5") (pintype "passive"))
    )
    (net (code "52") (name "/SCL") (class "Default")
      (node (ref "IC2") (pin "58") (pinfunction "PB6/I2C1_SCL/USART1_TX_58") (pintype "bidirectional"))
      (node (ref "R54") (pin "2") (pinfunction "2_2") (pintype "passive"))
      (node (ref "R59") (pin "1") (pinfunction "1_1") (pintype "passive"))
    )
    (net (code "53") (name "/SDA") (class "Default")
      (node (ref "IC2") (pin "59") (pinfunction "PB7/I2C1_SDA/USART1_RX_59") (pintype "bidirectional"))
      (node (ref "R53") (pin "2") (pinfunction "2_2") (pintype "passive"))
      (node (ref "R58") (pin "1") (pinfunction "1_1") (pintype "passive"))
    )
    (net (code "54") (name "/SWCLK") (class "Default")
      (node (ref "IC2") (pin "49") (pinfunction "PA14/JTCK-SWCLK_49") (pintype "bidirectional"))
      (node (ref "J3") (pin "3") (pinfunction "3_3") (pintype "passive"))
    )
    (net (code "55") (name "/SWDIO") (class "Default")
      (node (ref "IC2") (pin "46") (pinfunction "PA13/JTMS-SWDIO_46") (pintype "bidirectional"))
      (node (ref "J3") (pin "2") (pinfunction "2_2") (pintype "passive"))
    )
    (net (code "56") (name "/TRIG") (class "Default")
      (node (ref "IC2") (pin "43") (pinfunction "PA10/USART1_RX/TIM1_CH3_43") (pintype "bidirectional"))
      (node (ref "R27") (pin "1") (pinfunction "1_1") (pintype "passive"))
    )
    (net (code "57") (name "/UART4_RX") (class "Default")
      (node (ref "IC2") (pin "52") (pinfunction "PC11/UART4_RX/SDIO_D3/USART3_RX_52") (pintype "bidirectional"))
      (node (ref "R79") (pin "2") (pinfunction "2_2") (pintype "passive"))
    )
    (net (code "58") (name "/UART4_TX") (class "Default")
      (node (ref "IC2") (pin "51") (pinfunction "PC10/UART4_TX/SDIO_D2/USART3_TX_51") (pintype "bidirectional"))
      (node (ref "R78") (pin "2") (pinfunction "2_2") (pintype "passive"))
    )
    (net (code "59") (name "/USART3_RX") (class "Default")
      (node (ref "IC2") (pin "30") (pinfunction "PB11/I2C2_SDA/USART3_RX_30") (pintype "bidirectional"))
      (node (ref "R97") (pin "1") (pinfunction "1_1") (pintype "passive"))
    )
    (net (code "60") (name "/USART3_TX") (class "Default")
      (node (ref "IC2") (pin "29") (pinfunction "PB10/I2C2_SCL/USART3_TX_29") (pintype "bidirectional"))
      (node (ref "R98") (pin "1") (pinfunction "1_1") (pintype "passive"))
    )
    (net (code "61") (name "/VIN_AD") (class "Default")
      (node (ref "C38") (pin "1") (pintype "passive"))
      (node (ref "IC2") (pin "9") (pinfunction "PC1/ADC123_IN11_9") (pintype "bidirectional"))
      (node (ref "R51") (pin "1") (pinfunction "1_1") (pintype "passive"))
      (node (ref "R52") (pin "2") (pinfunction "2_2") (pintype "passive"))
    )
    (net (code "62") (name "GND") (class "Default")
      (node (ref "3.3V") (pin "2") (pinfunction "K_2") (pintype "passive"))
      (node (ref "5V") (pin "2") (pinfunction "K_2") (pintype "passive"))
      (node (ref "C1") (pin "2") (pintype "passive"))
      (node (ref "C10") (pin "2") (pintype "passive"))
      (node (ref "C11") (pin "2") (pintype "passive"))
      (node (ref "C12") (pin "2") (pintype "passive"))
      (node (ref "C13") (pin "2") (pintype "passive"))
      (node (ref "C14") (pin "2") (pintype "passive"))
      (node (ref "C15") (pin "1") (pintype "passive"))
      (node (ref "C16") (pin "1") (pintype "passive"))
      (node (ref "C2") (pin "2") (pintype "passive"))
      (node (ref "C22") (pin "2") (pintype "passive"))
      (node (ref "C24") (pin "2") (pintype "passive"))
      (node (ref "C27") (pin "2") (pinfunction "2_2") (pintype "passive"))
      (node (ref "C28") (pin "2") (pinfunction "2_2") (pintype "passive"))
      (node (ref "C3") (pin "2") (pintype "passive"))
      (node (ref "C31") (pin "2") (pinfunction "2_2") (pintype "passive"))
      (node (ref "C32") (pin "2") (pinfunction "2_2") (pintype "passive"))
      (node (ref "C37") (pin "2") (pintype "passive"))
      (node (ref "C38") (pin "2") (pintype "passive"))
      (node (ref "C39") (pin "2") (pinfunction "2_2") (pintype "passive"))
      (node (ref "C4") (pin "2") (pintype "passive"))
      (node (ref "C42") (pin "2") (pinfunction "2_2") (pintype "passive"))
      (node (ref "C45") (pin "2") (pintype "passive"))
      (node (ref "C46") (pin "2") (pintype "passive"))
      (node (ref "C47") (pin "2") (pintype "passive"))
      (node (ref "C48") (pin "2") (pintype "passive"))
      (node (ref "C49") (pin "2") (pintype "passive"))
      (node (ref "C5") (pin "2") (pintype "passive"))
      (node (ref "C50") (pin "2") (pintype "passive"))
      (node (ref "C51") (pin "2") (pintype "passive"))
      (node (ref "C53") (pin "2") (pintype "passive"))
      (node (ref "C54") (pin "2") (pintype "passive"))
      (node (ref "C59") (pin "2") (pinfunction "2_2") (pintype "passive"))
      (node (ref "C6") (pin "2") (pintype "passive"))
      (node (ref "C60") (pin "2") (pinfunction "2_2") (pintype "passive"))
      (node (ref "C61") (pin "2") (pinfunction "2_2") (pintype "passive"))
      (node (ref "C62") (pin "2") (pinfunction "2_2") (pintype "passive"))
      (node (ref "C63") (pin "2") (pinfunction "2_2") (pintype "passive"))
      (node (ref "C64") (pin "2") (pintype "passive"))
      (node (ref "C9") (pin "2") (pintype "passive"))
      (node (ref "G1") (pin "1") (pinfunction "GND_1") (pintype "passive"))
      (node (ref "IC2") (pin "12") (pinfunction "VSSA_12") (pintype "power_in"))
      (node (ref "IC2") (pin "18") (pinfunction "VSS_4_18") (pintype "power_in"))
      (node (ref "IC2") (pin "31") (pinfunction "VSS_1_31") (pintype "power_in"))
      (node (ref "IC2") (pin "47") (pinfunction "VSS_2_47") (pintype "power_in"))
      (node (ref "IC2") (pin "63") (pinfunction "VSS_3_63") (pintype "power_in"))
      (node (ref "J-IN") (pin "3") (pinfunction "G_3") (pintype "passive"))
      (node (ref "J3") (pin "4") (pinfunction "4_4") (pintype "passive"))
      (node (ref "JP1") (pin "3") (pinfunction "3_3") (pintype "passive"))
      (node (ref "JP10") (pin "3") (pinfunction "3_3") (pintype "passive"))
      (node (ref "JP11") (pin "3") (pinfunction "3_3") (pintype "passive"))
      (node (ref "JP12") (pin "3") (pinfunction "3_3") (pintype "passive"))
      (node (ref "JP13") (pin "3") (pinfunction "3_3") (pintype "passive"))
      (node (ref "JP14") (pin "2") (pinfunction "GND_2") (pintype "passive"))
      (node (ref "JP2") (pin "3") (pinfunction "3_3") (pintype "passive"))
      (node (ref "JP3") (pin "3") (pinfunction "3_3") (pintype "passive"))
      (node (ref "JP4") (pin "3") (pinfunction "3_3") (pintype "passive"))
      (node (ref "JP5") (pin "3") (pinfunction "3_3") (pintype "passive"))
      (node (ref "JP6") (pin "3") (pinfunction "3_3") (pintype "passive"))
      (node (ref "JP7") (pin "3") (pinfunction "3_3") (pintype "passive"))
      (node (ref "JP8") (pin "3") (pinfunction "3_3") (pintype "passive"))
      (node (ref "JP9") (pin "3") (pinfunction "3_3") (pintype "passive"))
      (node (ref "LED1") (pin "2") (pinfunction "K_2") (pintype "passive"))
      (node (ref "LED2") (pin "2") (pinfunction "K_2") (pintype "passive"))
      (node (ref "LED3") (pin "2") (pinfunction "K_2") (pintype "passive"))
      (node (ref "LED4") (pin "2") (pinfunction "K_2") (pintype "passive"))
      (node (ref "P1") (pin "4") (pinfunction "4_4") (pintype "passive"))
      (node (ref "P3") (pin "4") (pinfunction "4_4") (pintype "passive"))
      (node (ref "P4") (pin "5") (pinfunction "5_5") (pintype "passive"))
      (node (ref "Q1") (pin "2") (pinfunction "E_2") (pintype "passive"))
      (node (ref "R100") (pin "1") (pinfunction "1_1") (pintype "passive"))
      (node (ref "R51") (pin "2") (pinfunction "2_2") (pintype "passive"))
      (node (ref "R57") (pin "1") (pinfunction "1_1") (pintype "passive"))
      (node (ref "R99") (pin "1") (pinfunction "1_1") (pintype "passive"))
      (node (ref "RST") (pin "2") (pinfunction "NO_2") (pintype "passive"))
      (node (ref "SB2") (pin "2") (pinfunction "NO_2") (pintype "passive"))
      (node (ref "SB3") (pin "2") (pinfunction "NO_2") (pintype "passive"))
      (node (ref "U1") (pin "4") (pinfunction "GND_4") (pintype "passive"))
      (node (ref "U10") (pin "4") (pinfunction "GND_4") (pintype "passive"))
      (node (ref "U11") (pin "4") (pinfunction "GND_4") (pintype "passive"))
      (node (ref "U12") (pin "4") (pinfunction "GND_4") (pintype "passive"))
      (node (ref "U13") (pin "4") (pinfunction "GND_4") (pintype "passive"))
      (node (ref "U14") (pin "4") (pinfunction "GND_4") (pintype "passive"))
      (node (ref "U2") (pin "4") (pinfunction "GND_4") (pintype "passive"))
      (node (ref "U3") (pin "4") (pinfunction "GND_4") (pintype "passive"))
      (node (ref "U4") (pin "4") (pinfunction "GND_4") (pintype "passive"))
      (node (ref "U5") (pin "4") (pinfunction "GND_4") (pintype "passive"))
      (node (ref "U6") (pin "4") (pinfunction "GND_4") (pintype "passive"))
      (node (ref "U8") (pin "1") (pinfunction "CLKIN_1") (pintype "passive"))
      (node (ref "U8") (pin "11") (pinfunction "FSYNC_11") (pintype "passive"))
      (node (ref "U8") (pin "18") (pinfunction "GND_18") (pintype "passive"))
      (node (ref "U9") (pin "4") (pinfunction "GND_4") (pintype "passive"))
      (node (ref "V5+") (pin "1") (pinfunction "1_1") (pintype "passive"))
      (node (ref "VD2") (pin "1") (pinfunction "1_1") (pintype "passive"))
      (node (ref "VD3") (pin "1") (pinfunction "1_1") (pintype "passive"))
      (node (ref "VD4") (pin "1") (pinfunction "1_1") (pintype "passive"))
      (node (ref "VD5") (pin "1") (pinfunction "1_1") (pintype "passive"))
      (node (ref "X1") (pin "1") (pinfunction "GND_1") (pintype "passive"))
    )
    (net (code "63") (name "Net-(3.3V-A)") (class "Default")
      (node (ref "3.3V") (pin "1") (pinfunction "A_1") (pintype "passive"))
      (node (ref "R66") (pin "2") (pinfunction "2_2") (pintype "passive"))
    )
    (net (code "64") (name "Net-(5V-A)") (class "Default")
      (node (ref "5V") (pin "1") (pinfunction "A_1") (pintype "passive"))
      (node (ref "R67") (pin "2") (pinfunction "2_2") (pintype "passive"))
    )
    (net (code "65") (name "Net-(B1-A)") (class "Default")
      (node (ref "B1") (pin "1") (pinfunction "A_1") (pintype "passive"))
      (node (ref "R28") (pin "2") (pinfunction "2_2") (pintype "passive"))
    )
    (net (code "66") (name "Net-(B1-B)") (class "Default")
      (node (ref "B1") (pin "2") (pinfunction "B_2") (pintype "passive"))
      (node (ref "Q1") (pin "3") (pinfunction "C_3") (pintype "passive"))
    )
    (net (code "67") (name "Net-(JP14-OUT)") (class "Default")
      (node (ref "JP14") (pin "1") (pinfunction "OUT_1") (pintype "passive"))
      (node (ref "R89") (pin "2") (pinfunction "2_2") (pintype "passive"))
    )
    (net (code "68") (name "Net-(LED1-A)") (class "Default")
      (node (ref "LED1") (pin "1") (pinfunction "A_1") (pintype "passive"))
      (node (ref "R56") (pin "2") (pinfunction "2_2") (pintype "passive"))
    )
    (net (code "69") (name "Net-(LED2-A)") (class "Default")
      (node (ref "LED2") (pin "1") (pinfunction "A_1") (pintype "passive"))
      (node (ref "R55") (pin "2") (pinfunction "2_2") (pintype "passive"))
    )
    (net (code "70") (name "Net-(LED3-A)") (class "Default")
      (node (ref "LED3") (pin "1") (pinfunction "A_1") (pintype "passive"))
      (node (ref "R95") (pin "2") (pinfunction "2_2") (pintype "passive"))
    )
    (net (code "71") (name "Net-(LED4-A)") (class "Default")
      (node (ref "LED4") (pin "1") (pinfunction "A_1") (pintype "passive"))
      (node (ref "R96") (pin "2") (pinfunction "2_2") (pintype "passive"))
    )
    (net (code "72") (name "Net-(P1-Pad2)") (class "Default")
      (node (ref "P1") (pin "2") (pinfunction "2_2") (pintype "passive"))
      (node (ref "R78") (pin "1") (pinfunction "1_1") (pintype "passive"))
    )
    (net (code "73") (name "Net-(P1-Pad3)") (class "Default")
      (node (ref "P1") (pin "3") (pinfunction "3_3") (pintype "passive"))
      (node (ref "R79") (pin "1") (pinfunction "1_1") (pintype "passive"))
    )
    (net (code "74") (name "Net-(P3-Pad2)") (class "Default")
      (node (ref "P3") (pin "2") (pinfunction "2_2") (pintype "passive"))
      (node (ref "R27") (pin "2") (pinfunction "2_2") (pintype "passive"))
    )
    (net (code "75") (name "Net-(P3-Pad3)") (class "Default")
      (node (ref "P3") (pin "3") (pinfunction "3_3") (pintype "passive"))
      (node (ref "R29") (pin "2") (pinfunction "2_2") (pintype "passive"))
    )
    (net (code "76") (name "Net-(P4-Pad3)") (class "Default")
      (node (ref "P4") (pin "3") (pinfunction "3_3") (pintype "passive"))
      (node (ref "R97") (pin "2") (pinfunction "2_2") (pintype "passive"))
    )
    (net (code "77") (name "Net-(P4-Pad4)") (class "Default")
      (node (ref "P4") (pin "4") (pinfunction "4_4") (pintype "passive"))
      (node (ref "R98") (pin "2") (pinfunction "2_2") (pintype "passive"))
    )
    (net (code "78") (name "Net-(Q1-B)") (class "Default")
      (node (ref "Q1") (pin "1") (pinfunction "B_1") (pintype "passive"))
      (node (ref "R26") (pin "2") (pinfunction "2_2") (pintype "passive"))
    )
    (net (code "79") (name "Net-(SW1-Pad1)") (class "Default")
      (node (ref "SW1") (pin "1") (pinfunction "1_1") (pintype "passive"))
      (node (ref "VD1") (pin "2") (pinfunction "2_2") (pintype "passive"))
    )
    (net (code "80") (name "Net-(U1-A)") (class "Default")
      (node (ref "R14") (pin "2") (pinfunction "2_2") (pintype "passive"))
      (node (ref "U1") (pin "1") (pinfunction "A_1") (pintype "passive"))
    )
    (net (code "81") (name "Net-(U2-A)") (class "Default")
      (node (ref "R15") (pin "2") (pinfunction "2_2") (pintype "passive"))
      (node (ref "U2") (pin "1") (pinfunction "A_1") (pintype "passive"))
    )
    (net (code "82") (name "Net-(U3-A)") (class "Default")
      (node (ref "R16") (pin "2") (pinfunction "2_2") (pintype "passive"))
      (node (ref "U3") (pin "1") (pinfunction "A_1") (pintype "passive"))
    )
    (net (code "83") (name "Net-(U4-A)") (class "Default")
      (node (ref "R17") (pin "2") (pinfunction "2_2") (pintype "passive"))
      (node (ref "U4") (pin "1") (pinfunction "A_1") (pintype "passive"))
    )
    (net (code "84") (name "Net-(U5-A)") (class "Default")
      (node (ref "R20") (pin "2") (pinfunction "2_2") (pintype "passive"))
      (node (ref "U5") (pin "1") (pinfunction "A_1") (pintype "passive"))
    )
    (net (code "85") (name "Net-(U6-A)") (class "Default")
      (node (ref "R21") (pin "2") (pinfunction "2_2") (pintype "passive"))
      (node (ref "U6") (pin "1") (pinfunction "A_1") (pintype "passive"))
    )
    (net (code "86") (name "Net-(U8-AD0)") (class "Default")
      (node (ref "R57") (pin "2") (pinfunction "2_2") (pintype "passive"))
      (node (ref "U8") (pin "9") (pinfunction "AD0_9") (pintype "passive"))
    )
    (net (code "87") (name "Net-(U8-CPOUT)") (class "Default")
      (node (ref "C46") (pin "1") (pintype "passive"))
      (node (ref "U8") (pin "20") (pinfunction "CPOUT_20") (pintype "passive"))
    )
    (net (code "88") (name "Net-(U8-REGOUT)") (class "Default")
      (node (ref "C47") (pin "1") (pintype "passive"))
      (node (ref "U8") (pin "10") (pinfunction "REGOUT_10") (pintype "passive"))
    )
    (net (code "89") (name "Net-(U8-SCL)") (class "Default")
      (node (ref "R59") (pin "2") (pinfunction "2_2") (pintype "passive"))
      (node (ref "U8") (pin "23") (pinfunction "SCL_23") (pintype "passive"))
    )
    (net (code "90") (name "Net-(U8-SDA)") (class "Default")
      (node (ref "R58") (pin "2") (pinfunction "2_2") (pintype "passive"))
      (node (ref "U8") (pin "24") (pinfunction "SDA_24") (pintype "passive"))
    )
    (net (code "91") (name "Net-(U8-VDD)") (class "Default")
      (node (ref "C45") (pin "1") (pintype "passive"))
      (node (ref "R80") (pin "2") (pinfunction "2_2") (pintype "passive"))
      (node (ref "U8") (pin "13") (pinfunction "VDD_13") (pintype "passive"))
      (node (ref "U8") (pin "8") (pinfunction "VLOGIC_8") (pintype "passive"))
    )
    (net (code "92") (name "Net-(U9-A)") (class "Default")
      (node (ref "R61") (pin "2") (pinfunction "2_2") (pintype "passive"))
      (node (ref "U9") (pin "1") (pinfunction "A_1") (pintype "passive"))
    )
    (net (code "93") (name "Net-(U10-A)") (class "Default")
      (node (ref "R62") (pin "2") (pinfunction "2_2") (pintype "passive"))
      (node (ref "U10") (pin "1") (pinfunction "A_1") (pintype "passive"))
    )
    (net (code "94") (name "Net-(U11-A)") (class "Default")
      (node (ref "R63") (pin "2") (pinfunction "2_2") (pintype "passive"))
      (node (ref "U11") (pin "1") (pinfunction "A_1") (pintype "passive"))
    )
    (net (code "95") (name "Net-(U12-A)") (class "Default")
      (node (ref "R64") (pin "2") (pinfunction "2_2") (pintype "passive"))
      (node (ref "U12") (pin "1") (pinfunction "A_1") (pintype "passive"))
    )
    (net (code "96") (name "Net-(U13-A)") (class "Default")
      (node (ref "R65") (pin "2") (pinfunction "2_2") (pintype "passive"))
      (node (ref "U13") (pin "1") (pinfunction "A_1") (pintype "passive"))
    )
    (net (code "97") (name "Net-(U14-A)") (class "Default")
      (node (ref "R60") (pin "2") (pinfunction "2_2") (pintype "passive"))
      (node (ref "U14") (pin "1") (pinfunction "A_1") (pintype "passive"))
    )
    (net (code "98") (name "PW_IN") (class "Default")
      (node (ref "J-IN") (pin "1") (pinfunction "+_1") (pintype "passive"))
      (node (ref "VD1") (pin "1") (pinfunction "1_1") (pintype "passive"))
    )
    (net (code "99") (name "unconnected-(IC2A-PB1{slash}ADC12_IN9-Pad27)") (class "Default")
      (node (ref "IC2") (pin "27") (pinfunction "PB1/ADC12_IN9_27") (pintype "bidirectional+no_connect"))
    )
    (net (code "100") (name "unconnected-(IC2A-PB5{slash}I2C1_SMBA{slash}I2S3_SD{slash}SPI1_MOSI-Pad57)") (class "Default")
      (node (ref "IC2") (pin "57") (pinfunction "PB5/I2C1_SMBA/I2S3_SD/SPI1_MOSI_57") (pintype "bidirectional"))
    )
    (net (code "101") (name "unconnected-(IC2A-PC0{slash}ADC123_IN10-Pad8)") (class "Default")
      (node (ref "IC2") (pin "8") (pinfunction "PC0/ADC123_IN10_8") (pintype "bidirectional"))
    )
    (net (code "102") (name "unconnected-(IC2A-PC13-TAMPER-RTC-Pad2)") (class "Default")
      (node (ref "IC2") (pin "2") (pinfunction "PC13-TAMPER-RTC_2") (pintype "bidirectional+no_connect"))
    )
    (net (code "103") (name "unconnected-(IC2A-PC14-OSC32_IN-Pad3)") (class "Default")
      (node (ref "IC2") (pin "3") (pinfunction "PC14-OSC32_IN_3") (pintype "bidirectional+no_connect"))
    )
    (net (code "104") (name "unconnected-(IC2A-PC15-OSC32_OUT-Pad4)") (class "Default")
      (node (ref "IC2") (pin "4") (pinfunction "PC15-OSC32_OUT_4") (pintype "bidirectional+no_connect"))
    )
    (net (code "105") (name "unconnected-(P1-Pad1)") (class "Default")
      (node (ref "P1") (pin "1") (pinfunction "1_1") (pintype "passive+no_connect"))
    )
    (net (code "106") (name "unconnected-(P1-Pad6)") (class "Default")
      (node (ref "P1") (pin "6") (pinfunction "6_6") (pintype "passive+no_connect"))
    )
    (net (code "107") (name "unconnected-(P4-Pad1)") (class "Default")
      (node (ref "P4") (pin "1") (pinfunction "1_1") (pintype "passive+no_connect"))
    )
    (net (code "108") (name "unconnected-(U8-AUX_CL-Pad7)") (class "Default")
      (node (ref "U8") (pin "7") (pinfunction "AUX_CL_7") (pintype "passive+no_connect"))
    )
    (net (code "109") (name "unconnected-(U8-AUX_DA-Pad6)") (class "Default")
      (node (ref "U8") (pin "6") (pinfunction "AUX_DA_6") (pintype "passive+no_connect"))
    )
    (net (code "110") (name "unconnected-(U8-INT-Pad12)") (class "Default")
      (node (ref "U8") (pin "12") (pinfunction "INT_12") (pintype "passive+no_connect"))
    )
    (net (code "111") (name "unconnected-(U8-NC-Pad2)") (class "Default")
      (node (ref "U8") (pin "2") (pinfunction "NC_2") (pintype "passive+no_connect"))
    )
    (net (code "112") (name "unconnected-(U8-NC-Pad3)") (class "Default")
      (node (ref "U8") (pin "3") (pinfunction "NC_3") (pintype "passive+no_connect"))
    )
    (net (code "113") (name "unconnected-(U8-NC-Pad4)") (class "Default")
      (node (ref "U8") (pin "4") (pinfunction "NC_4") (pintype "passive+no_connect"))
    )
    (net (code "114") (name "unconnected-(U8-NC-Pad5)") (class "Default")
      (node (ref "U8") (pin "5") (pinfunction "NC_5") (pintype "passive+no_connect"))
    )
    (net (code "115") (name "unconnected-(U8-NC-Pad14)") (class "Default")
      (node (ref "U8") (pin "14") (pinfunction "NC_14") (pintype "passive+no_connect"))
    )
    (net (code "116") (name "unconnected-(U8-NC-Pad15)") (class "Default")
      (node (ref "U8") (pin "15") (pinfunction "NC_15") (pintype "passive+no_connect"))
    )
    (net (code "117") (name "unconnected-(U8-NC-Pad16)") (class "Default")
      (node (ref "U8") (pin "16") (pinfunction "NC_16") (pintype "passive+no_connect"))
    )
    (net (code "118") (name "unconnected-(U8-NC-Pad17)") (class "Default")
      (node (ref "U8") (pin "17") (pinfunction "NC_17") (pintype "passive+no_connect"))
    )
    (net (code "119") (name "unconnected-(U8-RESV-Pad19)") (class "Default")
      (node (ref "U8") (pin "19") (pinfunction "RESV_19") (pintype "passive+no_connect"))
    )
    (net (code "120") (name "unconnected-(U8-RESV-Pad21)") (class "Default")
      (node (ref "U8") (pin "21") (pinfunction "RESV_21") (pintype "passive+no_connect"))
    )
    (net (code "121") (name "unconnected-(U8-RESV-Pad22)") (class "Default")
      (node (ref "U8") (pin "22") (pinfunction "RESV_22") (pintype "passive+no_connect"))
    )
  )
)
